# BS4C_00006_03_EasyEDA_2025_07_22.net
KiCad netlist of a schematic drawn in EasyEDA Pro
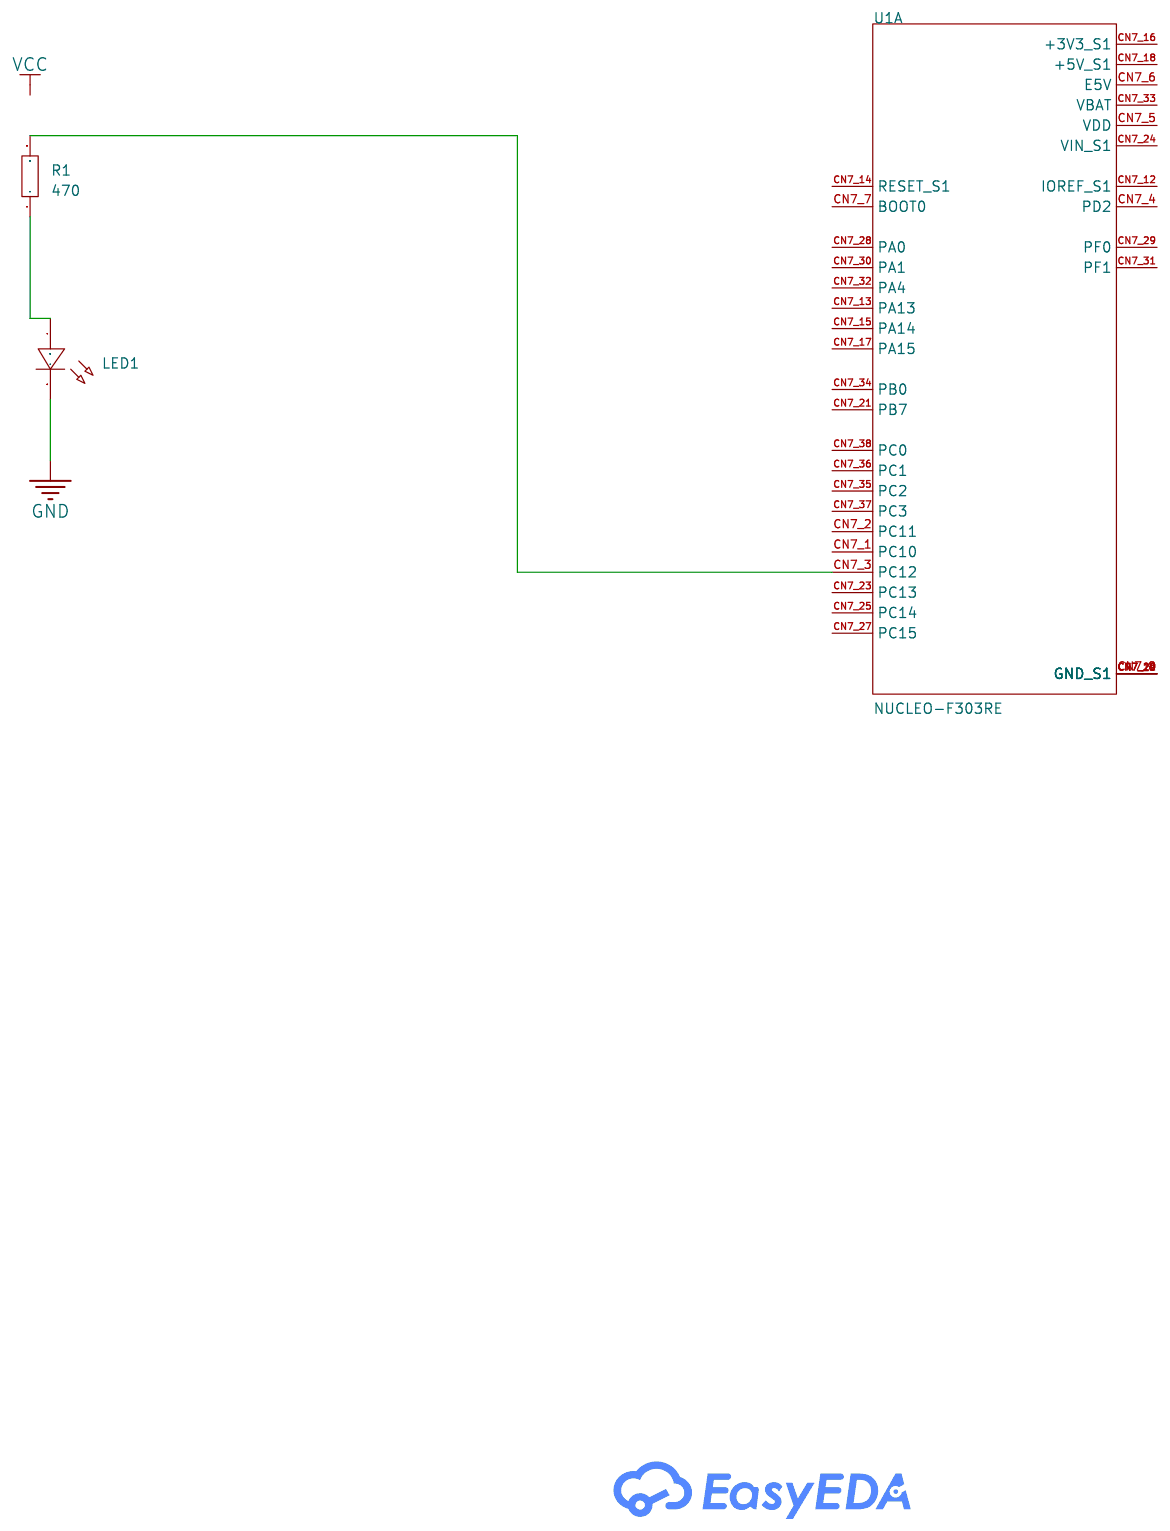
[diagram p0: schematic sheet]

(export (version "E")
  (design (tool "Eeschema 10.0.6"))
  (components
    (comp (ref "LED1")
      (value "~")
      (footprint "easyedapro:LED-TH_BD3.0-P2.54-FD")
      (libsource (lib "easyedapro") (part "LED_TH-R"))
    )
    (comp (ref "R1") (value "470") (footprint "easyedapro:R1210") (libsource (lib "easyedapro") (part "Res")))
    (comp (ref "U1") (value "NUCLEO-F303RE") (libsource (lib "easyedapro") (part "NUCLEO-F303RE")))
  )
  (nets
    (net (code "1") (name "GND") (class "Default")
      (node (ref "LED1") (pin "2") (pinfunction "A_2") (pintype "input"))
    )
    (net (code "2") (name "Net-(LED1-C)") (class "Default")
      (node (ref "LED1") (pin "1") (pinfunction "C_1") (pintype "input"))
      (node (ref "R1") (pin "1") (pinfunction "1_1") (pintype "input"))
    )
    (net (code "3") (name "Net-(U1A-GND_S1-PadCN7_19)") (class "Default")
      (node (ref "U1") (pin "CN7_19") (pinfunction "GND_S1_CN7_19") (pintype "unspecified"))
      (node (ref "U1") (pin "CN7_20") (pinfunction "GND_S1_CN7_20") (pintype "unspecified"))
      (node (ref "U1") (pin "CN7_22") (pinfunction "GND_S1_CN7_22") (pintype "unspecified"))
      (node (ref "U1") (pin "CN7_8") (pinfunction "GND_S1_CN7_8") (pintype "unspecified"))
    )
    (net (code "4") (name "Net-(U1A-PC12)") (class "Default")
      (node (ref "R1") (pin "2") (pinfunction "2_2") (pintype "input"))
      (node (ref "U1") (pin "CN7_3") (pinfunction "PC12_CN7_3") (pintype "bidirectional"))
    )
    (net (code "6") (name "unconnected-(U1A-+3V3_S1-PadCN7_16)") (class "Default")
      (node (ref "U1") (pin "CN7_16") (pinfunction "+3V3_S1_CN7_16") (pintype "unspecified"))
    )
    (net (code "7") (name "unconnected-(U1A-+5V_S1-PadCN7_18)") (class "Default")
      (node (ref "U1") (pin "CN7_18") (pinfunction "+5V_S1_CN7_18") (pintype "unspecified"))
    )
    (net (code "8") (name "unconnected-(U1A-BOOT0-PadCN7_7)") (class "Default")
      (node (ref "U1") (pin "CN7_7") (pinfunction "BOOT0_CN7_7") (pintype "bidirectional"))
    )
    (net (code "9") (name "unconnected-(U1A-E5V-PadCN7_6)") (class "Default")
      (node (ref "U1") (pin "CN7_6") (pinfunction "E5V_CN7_6") (pintype "unspecified"))
    )
    (net (code "10") (name "unconnected-(U1A-IOREF_S1-PadCN7_12)") (class "Default")
      (node (ref "U1") (pin "CN7_12") (pinfunction "IOREF_S1_CN7_12") (pintype "bidirectional"))
    )
    (net (code "11") (name "unconnected-(U1A-PA0-PadCN7_28)") (class "Default")
      (node (ref "U1") (pin "CN7_28") (pinfunction "PA0_CN7_28") (pintype "bidirectional"))
    )
    (net (code "12") (name "unconnected-(U1A-PA1-PadCN7_30)") (class "Default")
      (node (ref "U1") (pin "CN7_30") (pinfunction "PA1_CN7_30") (pintype "bidirectional"))
    )
    (net (code "13") (name "unconnected-(U1A-PA4-PadCN7_32)") (class "Default")
      (node (ref "U1") (pin "CN7_32") (pinfunction "PA4_CN7_32") (pintype "bidirectional"))
    )
    (net (code "14") (name "unconnected-(U1A-PA13-PadCN7_13)") (class "Default")
      (node (ref "U1") (pin "CN7_13") (pinfunction "PA13_CN7_13") (pintype "bidirectional"))
    )
    (net (code "15") (name "unconnected-(U1A-PA14-PadCN7_15)") (class "Default")
      (node (ref "U1") (pin "CN7_15") (pinfunction "PA14_CN7_15") (pintype "bidirectional"))
    )
    (net (code "16") (name "unconnected-(U1A-PA15-PadCN7_17)") (class "Default")
      (node (ref "U1") (pin "CN7_17") (pinfunction "PA15_CN7_17") (pintype "bidirectional"))
    )
    (net (code "17") (name "unconnected-(U1A-PB0-PadCN7_34)") (class "Default")
      (node (ref "U1") (pin "CN7_34") (pinfunction "PB0_CN7_34") (pintype "bidirectional"))
    )
    (net (code "18") (name "unconnected-(U1A-PB7-PadCN7_21)") (class "Default")
      (node (ref "U1") (pin "CN7_21") (pinfunction "PB7_CN7_21") (pintype "bidirectional"))
    )
    (net (code "19") (name "unconnected-(U1A-PC0-PadCN7_38)") (class "Default")
      (node (ref "U1") (pin "CN7_38") (pinfunction "PC0_CN7_38") (pintype "bidirectional"))
    )
    (net (code "20") (name "unconnected-(U1A-PC1-PadCN7_36)") (class "Default")
      (node (ref "U1") (pin "CN7_36") (pinfunction "PC1_CN7_36") (pintype "bidirectional"))
    )
    (net (code "21") (name "unconnected-(U1A-PC2-PadCN7_35)") (class "Default")
      (node (ref "U1") (pin "CN7_35") (pinfunction "PC2_CN7_35") (pintype "bidirectional"))
    )
    (net (code "22") (name "unconnected-(U1A-PC3-PadCN7_37)") (class "Default")
      (node (ref "U1") (pin "CN7_37") (pinfunction "PC3_CN7_37") (pintype "bidirectional"))
    )
    (net (code "23") (name "unconnected-(U1A-PC10-PadCN7_1)") (class "Default")
      (node (ref "U1") (pin "CN7_1") (pinfunction "PC10_CN7_1") (pintype "bidirectional"))
    )
    (net (code "24") (name "unconnected-(U1A-PC11-PadCN7_2)") (class "Default")
      (node (ref "U1") (pin "CN7_2") (pinfunction "PC11_CN7_2") (pintype "bidirectional"))
    )
    (net (code "25") (name "unconnected-(U1A-PC13-PadCN7_23)") (class "Default")
      (node (ref "U1") (pin "CN7_23") (pinfunction "PC13_CN7_23") (pintype "bidirectional"))
    )
    (net (code "26") (name "unconnected-(U1A-PC14-PadCN7_25)") (class "Default")
      (node (ref "U1") (pin "CN7_25") (pinfunction "PC14_CN7_25") (pintype "bidirectional"))
    )
    (net (code "27") (name "unconnected-(U1A-PC15-PadCN7_27)") (class "Default")
      (node (ref "U1") (pin "CN7_27") (pinfunction "PC15_CN7_27") (pintype "bidirectional"))
    )
    (net (code "28") (name "unconnected-(U1A-PD2-PadCN7_4)") (class "Default")
      (node (ref "U1") (pin "CN7_4") (pinfunction "PD2_CN7_4") (pintype "bidirectional"))
    )
    (net (code "29") (name "unconnected-(U1A-PF0-PadCN7_29)") (class "Default")
      (node (ref "U1") (pin "CN7_29") (pinfunction "PF0_CN7_29") (pintype "bidirectional"))
    )
    (net (code "30") (name "unconnected-(U1A-PF1-PadCN7_31)") (class "Default")
      (node (ref "U1") (pin "CN7_31") (pinfunction "PF1_CN7_31") (pintype "bidirectional"))
    )
    (net (code "31") (name "unconnected-(U1A-RESET_S1-PadCN7_14)") (class "Default")
      (node (ref "U1") (pin "CN7_14") (pinfunction "RESET_S1_CN7_14") (pintype "bidirectional"))
    )
    (net (code "32") (name "unconnected-(U1A-VBAT-PadCN7_33)") (class "Default")
      (node (ref "U1") (pin "CN7_33") (pinfunction "VBAT_CN7_33") (pintype "unspecified"))
    )
    (net (code "33") (name "unconnected-(U1A-VDD-PadCN7_5)") (class "Default")
      (node (ref "U1") (pin "CN7_5") (pinfunction "VDD_CN7_5") (pintype "unspecified"))
    )
    (net (code "34") (name "unconnected-(U1A-VIN_S1-PadCN7_24)") (class "Default")
      (node (ref "U1") (pin "CN7_24") (pinfunction "VIN_S1_CN7_24") (pintype "unspecified"))
    )
  )
)
